# MP2617B-SHEET.net
KiCad netlist of a schematic drawn in Altium Designer
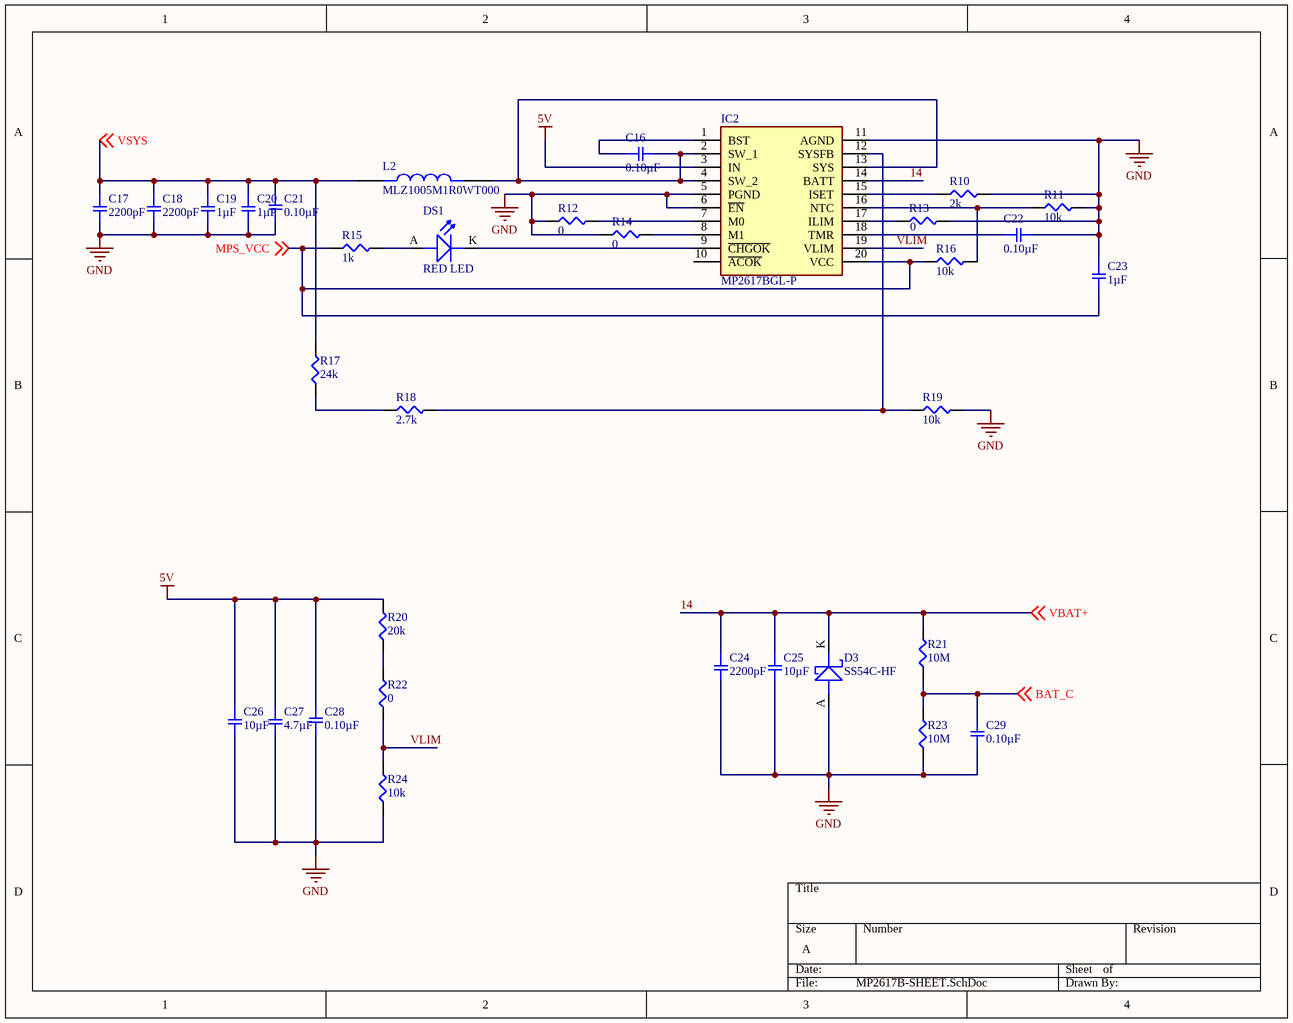
[diagram p0: MP2617B-SHEET.SchDoc]

(export (version "E")
  (design (tool "Eeschema 10.0.6"))
  (components
    (comp (ref "C16")
      (value "0.10µF")
      (footprint "SMD-0402C")
      (description "CAP CER 0.1UF 10V X5R 0402")
      (fields
        (field (name "DIGI-KEY PART NUMBER") "490-10008-1-ND")
        (field (name "PART NUMBER") "GRM152R61A104KE19D")
      )
      (libsource (lib "capacitor_murata_0402") (part "GRM152R61A104KE19D"))
    )
    (comp (ref "C17")
      (value "2200pF")
      (footprint "SMD-0402C")
      (description "CAP CER 22uF 10V X5R 0402")
      (fields
        (field (name "DIGI-KEY PART NUMBER") "490-8251-1-ND")
        (field (name "PART NUMBER") "GRM155R61A222KA01D")
      )
      (libsource (lib "capacitor_murata_0402") (part "GRM155R61A222KA01D"))
    )
    (comp (ref "C18")
      (value "2200pF")
      (footprint "SMD-0402C")
      (description "CAP CER 22uF 10V X5R 0402")
      (fields
        (field (name "DIGI-KEY PART NUMBER") "490-8251-1-ND")
        (field (name "PART NUMBER") "GRM155R61A222KA01D")
      )
      (libsource (lib "capacitor_murata_0402") (part "GRM155R61A222KA01D"))
    )
    (comp (ref "C19")
      (value "1µF")
      (footprint "SMD-0402C")
      (description "CAP CER 1UF 10V X7S 0402")
      (fields
        (field (name "DIGI-KEY PART NUMBER") "490-13409-1-ND")
        (field (name "PART NUMBER") "GCM155C71A105KE38D")
      )
      (libsource (lib "capacitor_murata_0402") (part "GCM155C71A105KE38D"))
    )
    (comp (ref "C20")
      (value "1µF")
      (footprint "SMD-0402C")
      (description "CAP CER 1UF 10V X7S 0402")
      (fields
        (field (name "DIGI-KEY PART NUMBER") "490-13409-1-ND")
        (field (name "PART NUMBER") "GCM155C71A105KE38D")
      )
      (libsource (lib "capacitor_murata_0402") (part "GCM155C71A105KE38D"))
    )
    (comp (ref "C21")
      (value "0.10µF")
      (footprint "SMD-0402C")
      (description "CAP CER 0.1UF 10V X5R 0402")
      (fields
        (field (name "DIGI-KEY PART NUMBER") "490-10008-1-ND")
        (field (name "PART NUMBER") "GRM152R61A104KE19D")
      )
      (libsource (lib "capacitor_murata_0402") (part "GRM152R61A104KE19D"))
    )
    (comp (ref "C22")
      (value "0.10µF")
      (footprint "SMD-0402C")
      (description "CAP CER 0.1UF 10V X5R 0402")
      (fields
        (field (name "DIGI-KEY PART NUMBER") "490-10008-1-ND")
        (field (name "PART NUMBER") "GRM152R61A104KE19D")
      )
      (libsource (lib "capacitor_murata_0402") (part "GRM152R61A104KE19D"))
    )
    (comp (ref "C23")
      (value "1µF")
      (footprint "SMD-0402C")
      (description "CAP CER 1UF 10V X7S 0402")
      (fields
        (field (name "DIGI-KEY PART NUMBER") "490-13409-1-ND")
        (field (name "PART NUMBER") "GCM155C71A105KE38D")
      )
      (libsource (lib "capacitor_murata_0402") (part "GCM155C71A105KE38D"))
    )
    (comp (ref "C24")
      (value "2200pF")
      (footprint "SMD-0402C")
      (description "CAP CER 22uF 10V X5R 0402")
      (fields
        (field (name "DIGI-KEY PART NUMBER") "490-8251-1-ND")
        (field (name "PART NUMBER") "GRM155R61A222KA01D")
      )
      (libsource (lib "capacitor_murata_0402") (part "GRM155R61A222KA01D"))
    )
    (comp (ref "C25")
      (value "10µF")
      (footprint "SMD-0402C")
      (description "CAP CER 10UF 10V X5R 0402")
      (fields
        (field (name "DIGI-KEY PART NUMBER") "490-13211-1-ND")
        (field (name "PART NUMBER") "GRJ155R60J106ME11D")
      )
      (libsource (lib "capacitor_murata_0402") (part "GRJ155R60J106ME11D"))
    )
    (comp (ref "C26")
      (value "10µF")
      (footprint "SMD-0402C")
      (description "CAP CER 10UF 10V X5R 0402")
      (fields
        (field (name "DIGI-KEY PART NUMBER") "490-13211-1-ND")
        (field (name "PART NUMBER") "GRJ155R60J106ME11D")
      )
      (libsource (lib "capacitor_murata_0402") (part "GRJ155R60J106ME11D"))
    )
    (comp (ref "C27")
      (value "4.7µF")
      (footprint "SMD-0402C")
      (description "CAP CER 4.7UF 10V X5R 0402")
      (fields
        (field (name "DIGI-KEY PART NUMBER") "490-13252-1-ND")
        (field (name "PART NUMBER") "ZRB15XR61A475KE01D")
      )
      (libsource (lib "capacitor_murata_0402") (part "ZRB15XR61A475KE01D"))
    )
    (comp (ref "C28")
      (value "0.10µF")
      (footprint "SMD-0402C")
      (description "CAP CER 0.1UF 10V X5R 0402")
      (fields
        (field (name "DIGI-KEY PART NUMBER") "490-10008-1-ND")
        (field (name "PART NUMBER") "GRM152R61A104KE19D")
      )
      (libsource (lib "capacitor_murata_0402") (part "GRM152R61A104KE19D"))
    )
    (comp (ref "C29")
      (value "0.10µF")
      (footprint "SMD-0402C")
      (description "CAP CER 0.1UF 10V X5R 0402")
      (fields
        (field (name "DIGI-KEY PART NUMBER") "490-10008-1-ND")
        (field (name "PART NUMBER") "GRM152R61A104KE19D")
      )
      (libsource (lib "capacitor_murata_0402") (part "GRM152R61A104KE19D"))
    )
    (comp (ref "D3")
      (value "SS54C-HF")
      (footprint "DIO_SMC_DO-214AB")
      (description "Schottky Diodes & Rectifiers 5A,40V,SM SCHOTTKY RECT")
      (fields (field (name "MANUFACTURER") "Vishay Semiconductors"))
      (libsource (lib "ESTEEMPCBLIB") (part "DIO-S_0.42-40V-5A-DO-214AB"))
    )
    (comp (ref "DS1")
      (value "RED LED")
      (footprint "LED_0805")
      (description "Red 631nm LED Indication - Discrete 2V 0805 (2012 Metric)")
      (fields
        (field (name "MANUFACTURER") "Vishay Lite-On")
        (field (name "MANUFACTURER PART NUMBER") "LTST-C171KRKT")
      )
      (libsource (lib "ESTEEMPCBLIB") (part "LED_RED-2V-20mA-0805"))
    )
    (comp (ref "IC2")
      (value "MP2617BGL-P")
      (footprint "SamacSys:MP2617AGLP")
      (description "Integrated Circuit")
      (fields (field (name "MOUSER PART NUMBER") "946-MP2617BGL-P"))
      (libsource (lib "*") (part "MP2617BGL-P"))
    )
    (comp (ref "L2")
      (value "MLZ1005M1R0WT000")
      (footprint "MLZ1005M1R0WT000:IND_MLZ1005M1R0WT000")
      (fields (field (name "MF") "{'manufacturer': u'TDK'}"))
      (libsource (lib "*") (part "MLZ1005M1R0WT000"))
    )
    (comp (ref "R10")
      (value "2k")
      (footprint "SMD-0402-RES")
      (description "RES SMD 2K OHM 5% 1/10W 0402")
      (fields (field (name "PART NUMBER") "ERJ-2GEJ202X") (field (name "DIGI-KEY PART NUMBER") "P2.0KJCT-ND"))
      (libsource (lib "Panasonic_ERJ_0402") (part "ERJ-2GEJ202X"))
    )
    (comp (ref "R11")
      (value "10k")
      (footprint "SMD-0402-RES")
      (description "RES SMD 10K OHM 5% 1/10W 0402")
      (fields (field (name "PART NUMBER") "ERJ-2GEJ103X") (field (name "DIGI-KEY PART NUMBER") "P10KJCT-ND"))
      (libsource (lib "Panasonic_ERJ_0402") (part "ERJ-2GEJ103X"))
    )
    (comp (ref "R12")
      (value "0")
      (footprint "SMD-0402-RES")
      (description "RES SMD 0.047 OHM 1% 1/4W 0402")
      (fields
        (field (name "PART NUMBER") "ERJ-2BWFR047X")
        (field (name "DIGI-KEY PART NUMBER") "P.047ATCT-ND")
      )
      (libsource (lib "Panasonic_ERJ_0402") (part "ERJ-2BWFR047X"))
    )
    (comp (ref "R13")
      (value "0")
      (footprint "SMD-0402-RES")
      (description "RES SMD 0.047 OHM 1% 1/4W 0402")
      (fields
        (field (name "PART NUMBER") "ERJ-2BWFR047X")
        (field (name "DIGI-KEY PART NUMBER") "P.047ATCT-ND")
      )
      (libsource (lib "Panasonic_ERJ_0402") (part "ERJ-2BWFR047X"))
    )
    (comp (ref "R14")
      (value "0")
      (footprint "SMD-0402-RES")
      (description "RES SMD 0.047 OHM 1% 1/4W 0402")
      (fields
        (field (name "PART NUMBER") "ERJ-2BWFR047X")
        (field (name "DIGI-KEY PART NUMBER") "P.047ATCT-ND")
      )
      (libsource (lib "Panasonic_ERJ_0402") (part "ERJ-2BWFR047X"))
    )
    (comp (ref "R15")
      (value "1k")
      (footprint "SMD-0402-RES")
      (description "RES SMD 1K OHM 5% 1/10W 0402")
      (fields (field (name "PART NUMBER") "ERJ-2GEJ102X") (field (name "DIGI-KEY PART NUMBER") "P1.0KJCT-ND"))
      (libsource (lib "Panasonic_ERJ_0402") (part "ERJ-2GEJ102X"))
    )
    (comp (ref "R16")
      (value "10k")
      (footprint "SMD-0402-RES")
      (description "RES SMD 10K OHM 5% 1/10W 0402")
      (fields (field (name "PART NUMBER") "ERJ-2GEJ103X") (field (name "DIGI-KEY PART NUMBER") "P10KJCT-ND"))
      (libsource (lib "Panasonic_ERJ_0402") (part "ERJ-2GEJ103X"))
    )
    (comp (ref "R17")
      (value "24k")
      (footprint "SMD-0402-RES")
      (description "RES SMD 24K OHM 5% 1/10W 0402")
      (fields (field (name "PART NUMBER") "ERJ-2GEJ243X") (field (name "DIGI-KEY PART NUMBER") "P24KJCT-ND"))
      (libsource (lib "Panasonic_ERJ_0402") (part "ERJ-2GEJ243X"))
    )
    (comp (ref "R18")
      (value "2.7k")
      (footprint "SMD-0402-RES")
      (description "RES SMD 2.7K OHM 5% 1/10W 0402")
      (fields (field (name "PART NUMBER") "ERJ-2GEJ272X") (field (name "DIGI-KEY PART NUMBER") "P2.7KJCT-ND"))
      (libsource (lib "Panasonic_ERJ_0402") (part "ERJ-2GEJ272X"))
    )
    (comp (ref "R19")
      (value "10k")
      (footprint "SMD-0402-RES")
      (description "RES SMD 10K OHM 5% 1/10W 0402")
      (fields (field (name "PART NUMBER") "ERJ-2GEJ103X") (field (name "DIGI-KEY PART NUMBER") "P10KJCT-ND"))
      (libsource (lib "Panasonic_ERJ_0402") (part "ERJ-2GEJ103X"))
    )
    (comp (ref "R20")
      (value "20k")
      (footprint "SMD-0402-RES")
      (description "RES SMD 20K OHM 5% 1/10W 0402")
      (fields (field (name "PART NUMBER") "ERJ-2GEJ203X") (field (name "DIGI-KEY PART NUMBER") "P20KJCT-ND"))
      (libsource (lib "Panasonic_ERJ_0402") (part "ERJ-2GEJ203X"))
    )
    (comp (ref "R21")
      (value "10M")
      (footprint "SMD-0402-RES")
      (description "RES SMD 10M OHM 5% 1/10W 0402")
      (fields (field (name "PART NUMBER") "ERJ-2GEJ106X") (field (name "DIGI-KEY PART NUMBER") "P10MJCT-ND"))
      (libsource (lib "Panasonic_ERJ_0402") (part "ERJ-2GEJ106X"))
    )
    (comp (ref "R22")
      (value "0")
      (footprint "SMD-0402-RES")
      (description "RES SMD 0.047 OHM 1% 1/4W 0402")
      (fields
        (field (name "PART NUMBER") "ERJ-2BWFR047X")
        (field (name "DIGI-KEY PART NUMBER") "P.047ATCT-ND")
      )
      (libsource (lib "Panasonic_ERJ_0402") (part "ERJ-2BWFR047X"))
    )
    (comp (ref "R23")
      (value "10M")
      (footprint "SMD-0402-RES")
      (description "RES SMD 10M OHM 5% 1/10W 0402")
      (fields (field (name "PART NUMBER") "ERJ-2GEJ106X") (field (name "DIGI-KEY PART NUMBER") "P10MJCT-ND"))
      (libsource (lib "Panasonic_ERJ_0402") (part "ERJ-2GEJ106X"))
    )
    (comp (ref "R24")
      (value "10k")
      (footprint "SMD-0402-RES")
      (description "RES SMD 10K OHM 5% 1/10W 0402")
      (fields (field (name "PART NUMBER") "ERJ-2GEJ103X") (field (name "DIGI-KEY PART NUMBER") "P10KJCT-ND"))
      (libsource (lib "Panasonic_ERJ_0402") (part "ERJ-2GEJ103X"))
    )
  )
  (nets
    (net (code "1") (name "/VLIM") (class "Default")
      (node (ref "IC2") (pin "19") (pinfunction "VLIM_19") (pintype "passive"))
      (node (ref "R22") (pin "1") (pinfunction "1_1") (pintype "passive"))
      (node (ref "R24") (pin "2") (pinfunction "2_2") (pintype "passive"))
    )
    (net (code "2") (name "5V") (class "Default")
      (node (ref "C26") (pin "1") (pinfunction "1_1") (pintype "passive"))
      (node (ref "C27") (pin "1") (pinfunction "1_1") (pintype "passive"))
      (node (ref "C28") (pin "2") (pinfunction "2_2") (pintype "passive"))
      (node (ref "IC2") (pin "3") (pinfunction "IN_3") (pintype "passive"))
      (node (ref "R20") (pin "2") (pinfunction "2_2") (pintype "passive"))
    )
    (net (code "3") (name "BAT_C") (class "Default")
      (node (ref "C29") (pin "2") (pinfunction "2_2") (pintype "passive"))
      (node (ref "R21") (pin "1") (pinfunction "1_1") (pintype "passive"))
      (node (ref "R23") (pin "2") (pinfunction "2_2") (pintype "passive"))
    )
    (net (code "4") (name "GND") (class "Default")
      (node (ref "C17") (pin "2") (pinfunction "2_2") (pintype "passive"))
      (node (ref "C18") (pin "2") (pinfunction "2_2") (pintype "passive"))
      (node (ref "C19") (pin "2") (pinfunction "2_2") (pintype "passive"))
      (node (ref "C20") (pin "2") (pinfunction "2_2") (pintype "passive"))
      (node (ref "C21") (pin "1") (pinfunction "1_1") (pintype "passive"))
      (node (ref "C22") (pin "2") (pinfunction "2_2") (pintype "passive"))
      (node (ref "C23") (pin "1") (pinfunction "1_1") (pintype "passive"))
      (node (ref "C24") (pin "2") (pinfunction "2_2") (pintype "passive"))
      (node (ref "C25") (pin "2") (pinfunction "2_2") (pintype "passive"))
      (node (ref "C26") (pin "2") (pinfunction "2_2") (pintype "passive"))
      (node (ref "C27") (pin "2") (pinfunction "2_2") (pintype "passive"))
      (node (ref "C28") (pin "1") (pinfunction "1_1") (pintype "passive"))
      (node (ref "C29") (pin "1") (pinfunction "1_1") (pintype "passive"))
      (node (ref "D3") (pin "A") (pinfunction "1_A") (pintype "passive"))
      (node (ref "IC2") (pin "11") (pinfunction "AGND_11") (pintype "passive"))
      (node (ref "IC2") (pin "5") (pinfunction "PGND_5") (pintype "passive"))
      (node (ref "IC2") (pin "6") (pinfunction "~{EN}_6") (pintype "passive"))
      (node (ref "R10") (pin "2") (pinfunction "2_2") (pintype "passive"))
      (node (ref "R11") (pin "2") (pinfunction "2_2") (pintype "passive"))
      (node (ref "R12") (pin "1") (pinfunction "1_1") (pintype "passive"))
      (node (ref "R13") (pin "2") (pinfunction "2_2") (pintype "passive"))
      (node (ref "R14") (pin "1") (pinfunction "1_1") (pintype "passive"))
      (node (ref "R19") (pin "2") (pinfunction "2_2") (pintype "passive"))
      (node (ref "R23") (pin "1") (pinfunction "1_1") (pintype "passive"))
      (node (ref "R24") (pin "1") (pinfunction "1_1") (pintype "passive"))
    )
    (net (code "5") (name "MPS_VCC") (class "Default")
      (node (ref "C23") (pin "2") (pinfunction "2_2") (pintype "passive"))
      (node (ref "IC2") (pin "20") (pinfunction "VCC_20") (pintype "passive"))
      (node (ref "R15") (pin "1") (pinfunction "1_1") (pintype "passive"))
      (node (ref "R16") (pin "1") (pinfunction "1_1") (pintype "passive"))
    )
    (net (code "6") (name "Net-(DS1-ANODE)") (class "Default")
      (node (ref "DS1") (pin "A") (pinfunction "ANODE_A") (pintype "passive"))
      (node (ref "R15") (pin "2") (pinfunction "2_2") (pintype "passive"))
    )
    (net (code "7") (name "Net-(DS1-CATHODE)") (class "Default")
      (node (ref "DS1") (pin "K") (pinfunction "CATHODE_K") (pintype "passive"))
      (node (ref "IC2") (pin "9") (pinfunction "~{CHGOK}_9") (pintype "passive"))
    )
    (net (code "8") (name "Net-(IC2-BST)") (class "Default")
      (node (ref "C16") (pin "1") (pinfunction "1_1") (pintype "passive"))
      (node (ref "IC2") (pin "1") (pinfunction "BST_1") (pintype "passive"))
    )
    (net (code "9") (name "Net-(IC2-ILIM)") (class "Default")
      (node (ref "IC2") (pin "17") (pinfunction "ILIM_17") (pintype "passive"))
      (node (ref "R13") (pin "1") (pinfunction "1_1") (pintype "passive"))
    )
    (net (code "10") (name "Net-(IC2-ISET)") (class "Default")
      (node (ref "IC2") (pin "15") (pinfunction "ISET_15") (pintype "passive"))
      (node (ref "R10") (pin "1") (pinfunction "1_1") (pintype "passive"))
    )
    (net (code "11") (name "Net-(IC2-M0)") (class "Default")
      (node (ref "IC2") (pin "7") (pinfunction "M0_7") (pintype "passive"))
      (node (ref "R12") (pin "2") (pinfunction "2_2") (pintype "passive"))
    )
    (net (code "12") (name "Net-(IC2-M1)") (class "Default")
      (node (ref "IC2") (pin "8") (pinfunction "M1_8") (pintype "passive"))
      (node (ref "R14") (pin "2") (pinfunction "2_2") (pintype "passive"))
    )
    (net (code "13") (name "Net-(IC2-NTC)") (class "Default")
      (node (ref "IC2") (pin "16") (pinfunction "NTC_16") (pintype "passive"))
      (node (ref "R11") (pin "1") (pinfunction "1_1") (pintype "passive"))
      (node (ref "R16") (pin "2") (pinfunction "2_2") (pintype "passive"))
    )
    (net (code "14") (name "Net-(IC2-SW_1)") (class "Default")
      (node (ref "C16") (pin "2") (pinfunction "2_2") (pintype "passive"))
      (node (ref "IC2") (pin "13") (pinfunction "SYS_13") (pintype "passive"))
      (node (ref "IC2") (pin "2") (pinfunction "SW_1_2") (pintype "passive"))
      (node (ref "IC2") (pin "4") (pinfunction "SW_2_4") (pintype "passive"))
      (node (ref "L2") (pin "2") (pinfunction "2_2") (pintype "passive"))
    )
    (net (code "15") (name "Net-(IC2-SYSFB)") (class "Default")
      (node (ref "IC2") (pin "12") (pinfunction "SYSFB_12") (pintype "passive"))
      (node (ref "R18") (pin "2") (pinfunction "2_2") (pintype "passive"))
      (node (ref "R19") (pin "1") (pinfunction "1_1") (pintype "passive"))
    )
    (net (code "16") (name "Net-(IC2-TMR)") (class "Default")
      (node (ref "C22") (pin "1") (pinfunction "1_1") (pintype "passive"))
      (node (ref "IC2") (pin "18") (pinfunction "TMR_18") (pintype "passive"))
    )
    (net (code "17") (name "Net-(R17-Pad1)") (class "Default")
      (node (ref "R17") (pin "1") (pinfunction "1_1") (pintype "passive"))
      (node (ref "R18") (pin "1") (pinfunction "1_1") (pintype "passive"))
    )
    (net (code "18") (name "Net-(R20-Pad1)") (class "Default")
      (node (ref "R20") (pin "1") (pinfunction "1_1") (pintype "passive"))
      (node (ref "R22") (pin "2") (pinfunction "2_2") (pintype "passive"))
    )
    (net (code "19") (name "VBAT+") (class "Default")
      (node (ref "C24") (pin "1") (pinfunction "1_1") (pintype "passive"))
      (node (ref "C25") (pin "1") (pinfunction "1_1") (pintype "passive"))
      (node (ref "D3") (pin "K") (pinfunction "2_K") (pintype "passive"))
      (node (ref "IC2") (pin "14") (pinfunction "BATT_14") (pintype "passive"))
      (node (ref "R21") (pin "2") (pinfunction "2_2") (pintype "passive"))
    )
    (net (code "20") (name "VSYS") (class "Default")
      (node (ref "C17") (pin "1") (pinfunction "1_1") (pintype "passive"))
      (node (ref "C18") (pin "1") (pinfunction "1_1") (pintype "passive"))
      (node (ref "C19") (pin "1") (pinfunction "1_1") (pintype "passive"))
      (node (ref "C20") (pin "1") (pinfunction "1_1") (pintype "passive"))
      (node (ref "C21") (pin "2") (pinfunction "2_2") (pintype "passive"))
      (node (ref "L2") (pin "1") (pinfunction "1_1") (pintype "passive"))
      (node (ref "R17") (pin "2") (pinfunction "2_2") (pintype "passive"))
    )
    (net (code "21") (name "unconnected-(IC2-~{ACOK}-Pad10)") (class "Default")
      (node (ref "IC2") (pin "10") (pinfunction "~{ACOK}_10") (pintype "passive"))
    )
  )
)
